# Sheet1.net
KiCad netlist of a schematic drawn in Altium Designer
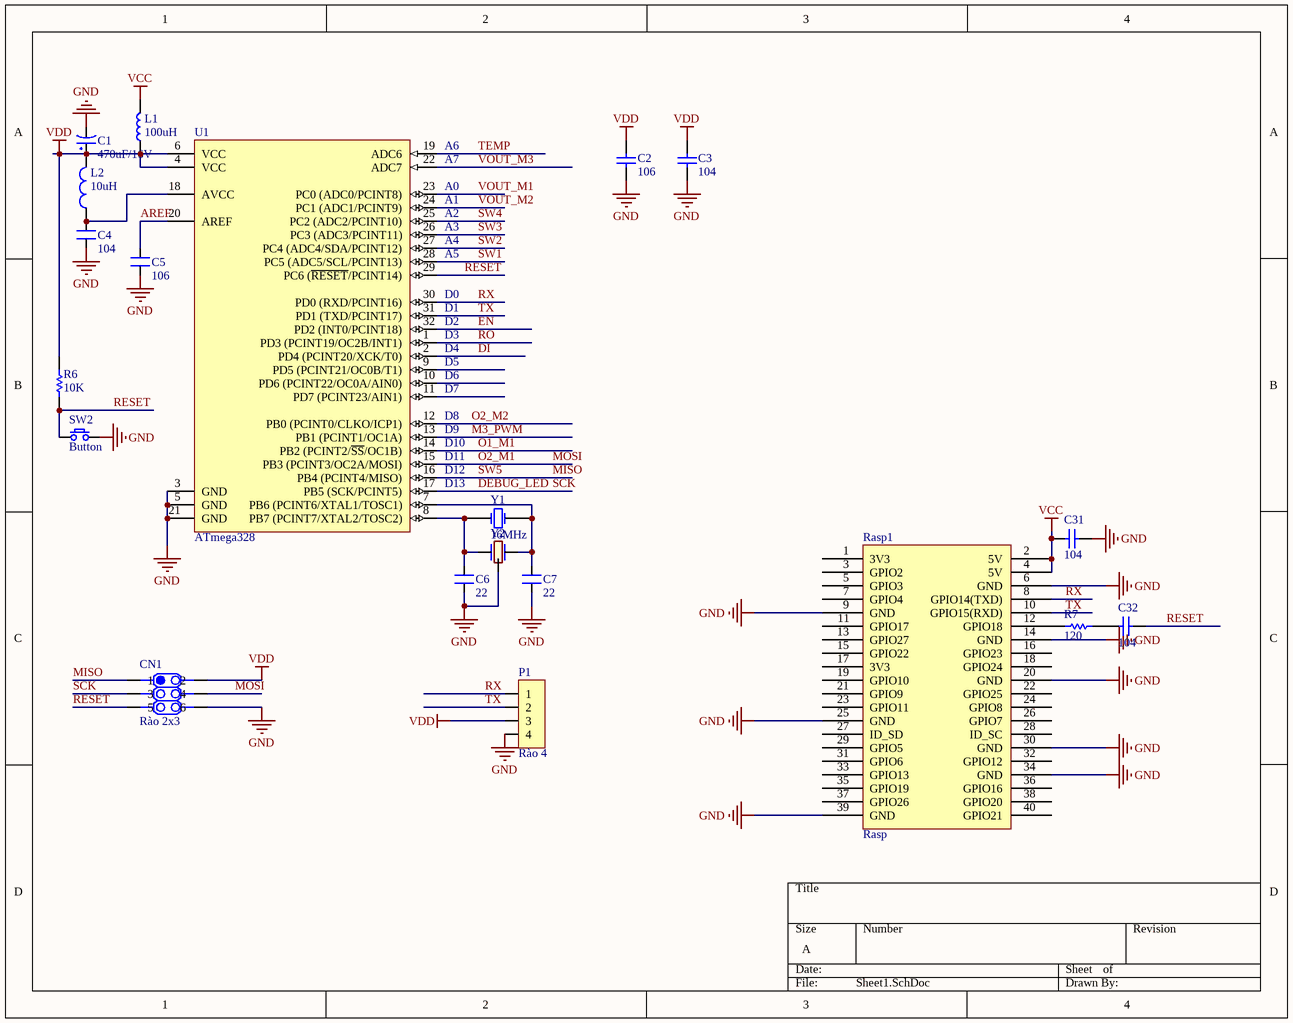
[diagram p0: Sheet1.SchDoc]

(export (version "E")
  (design (tool "Eeschema 10.0.6"))
  (components
    (comp (ref "C1")
      (value "470uF/16V")
      (footprint "WCAP-PSHP 8x8.7x3.1")
      (description "Cap 1000uF/16V - 220uF/50V")
      (libsource (lib "syhaunguyen") (part "CP4"))
    )
    (comp (ref "C2")
      (value "106")
      (footprint "C 0805 (2012)")
      (description "Capacitor non-pol")
      (libsource (lib "BKIT4U_LIB") (part "Capacitor NP"))
    )
    (comp (ref "C3")
      (value "104")
      (footprint "C 0805 (2012)")
      (description "Capacitor non-pol")
      (libsource (lib "BKIT4U_LIB") (part "Capacitor NP"))
    )
    (comp (ref "C4")
      (value "104")
      (footprint "R 0805 (2012)")
      (description "Cap np 104 => 105pF")
      (libsource (lib "syhaunguyen") (part "CN2"))
    )
    (comp (ref "C5")
      (value "106")
      (footprint "R 0805 (2012)")
      (description "Cap np  1pF - 472pF")
      (libsource (lib "syhaunguyen") (part "CN1"))
    )
    (comp (ref "C6")
      (value "22")
      (footprint "C 0805 (2012)")
      (description "Cap np 104 => 105pF")
      (libsource (lib "syhaunguyen") (part "CN2"))
    )
    (comp (ref "C7")
      (value "22")
      (footprint "C 0805 (2012)")
      (description "Cap np 104 => 105pF")
      (libsource (lib "syhaunguyen") (part "CN2"))
    )
    (comp (ref "C31")
      (value "104")
      (footprint "C 0805 (2012)")
      (description "Capacitor non-pol")
      (libsource (lib "BKIT4U_LIB") (part "Capacitor NP"))
    )
    (comp (ref "C32")
      (value "104")
      (footprint "C 0805 (2012)")
      (description "Capacitor non-pol")
      (libsource (lib "BKIT4U_LIB") (part "Capacitor NP"))
    )
    (comp (ref "CN1")
      (value "Rào 2x3")
      (footprint "Header 3x2")
      (description "Header 2x3")
      (fields (field (name "PUBLISHER") "Hoang Nguyen"))
      (libsource (lib "phong") (part "CON.HDR2x3"))
    )
    (comp (ref "L1")
      (value "100uH")
      (footprint "Inductor SMD 0805 (2012)")
      (description "Inductor")
      (libsource (lib "BKIT4U_LIB") (part "Inductor"))
    )
    (comp (ref "L2")
      (value "10uH")
      (footprint "R 0805 (2012)")
      (description "Inductor")
      (libsource (lib "syhaunguyen") (part "L1"))
    )
    (comp (ref "P1")
      (value "Rào 4")
      (footprint "Header 4")
      (description "Header, 4-Pin")
      (libsource (lib "BKIT4U_LIB") (part "Header 4"))
    )
    (comp (ref "R6")
      (value "10K")
      (footprint "R 0805 (2012)")
      (description "Resistor")
      (fields (field (name "PUBLISHER") "Altium Limited"))
      (libsource (lib "phong") (part "Resistor"))
    )
    (comp (ref "R7")
      (value "120")
      (footprint "R 0805 (2012)")
      (description "Resistor")
      (fields (field (name "PUBLISHER") "Altium Limited"))
      (libsource (lib "BKIT4U_LIB") (part "Resistor"))
    )
    (comp (ref "Rasp1")
      (value "Rasp")
      (footprint "Raspberry Pi 3B")
      (libsource (lib "Raspberry Pi 3B") (part "Rasp"))
    )
    (comp (ref "SW2")
      (value "Button")
      (footprint "SW/2/SMD")
      (description "Tact switch 2 pin")
      (libsource (lib "BKIT4U_LIB") (part "SW SPST"))
    )
    (comp (ref "U1")
      (value "ATmega328")
      (footprint "QFP32N")
      (fields (field (name "PUBLISHER") "Altium Limited"))
      (libsource (lib "Atmel Microcontroller 8-Bit megaAVR") (part "ATmega328-AU"))
    )
    (comp (ref "Y1")
      (value "16MHz")
      (footprint "XTAL")
      (description "Crystal Oscillator")
      (fields (field (name "PUBLISHER") "Altium Limited"))
      (libsource (lib "phong") (part "XTAL"))
    )
    (comp (ref "Y2")
      (value "~")
      (footprint "Crystal SMD CSTCE")
      (libsource (lib "BKIT4U_LIB") (part "Crystal CSTCE"))
    )
  )
  (nets
    (net (code "1") (name "/AREF") (class "Default")
      (node (ref "C5") (pin "2") (pinfunction "2_2") (pintype "passive"))
      (node (ref "U1") (pin "20") (pinfunction "AREF_20") (pintype "passive"))
    )
    (net (code "2") (name "/DEBUG_LED") (class "Default")
      (node (ref "CN1") (pin "3") (pinfunction "3_3") (pintype "passive"))
      (node (ref "U1") (pin "17") (pinfunction "PB5_(SCK/PCINT5)_17") (pintype "bidirectional"))
    )
    (net (code "3") (name "/DI") (class "Default")
      (node (ref "U1") (pin "2") (pinfunction "PD4_(PCINT20/XCK/T0)_2") (pintype "bidirectional"))
    )
    (net (code "4") (name "/EN") (class "Default")
      (node (ref "U1") (pin "32") (pinfunction "PD2_(INT0/PCINT18)_32") (pintype "bidirectional"))
    )
    (net (code "5") (name "/M3_PWM") (class "Default")
      (node (ref "U1") (pin "13") (pinfunction "PB1_(PCINT1/OC1A)_13") (pintype "bidirectional"))
    )
    (net (code "6") (name "/MISO") (class "Default")
      (node (ref "CN1") (pin "1") (pinfunction "1_1") (pintype "passive"))
      (node (ref "U1") (pin "16") (pinfunction "PB4_(PCINT4/MISO)_16") (pintype "bidirectional"))
    )
    (net (code "7") (name "/MOSI") (class "Default")
      (node (ref "CN1") (pin "4") (pinfunction "4_4") (pintype "passive"))
      (node (ref "U1") (pin "15") (pinfunction "PB3_(PCINT3/OC2A/MOSI)_15") (pintype "bidirectional"))
    )
    (net (code "8") (name "/O1_M1") (class "Default")
      (node (ref "U1") (pin "14") (pinfunction "PB2_(PCINT2/~{SS}/OC1B)_14") (pintype "bidirectional"))
    )
    (net (code "9") (name "/O2_M2") (class "Default")
      (node (ref "U1") (pin "12") (pinfunction "PB0_(PCINT0/CLKO/ICP1)_12") (pintype "bidirectional"))
    )
    (net (code "10") (name "/RESET") (class "Default")
      (node (ref "C32") (pin "2") (pinfunction "2_2") (pintype "passive"))
      (node (ref "CN1") (pin "5") (pinfunction "5_5") (pintype "passive"))
      (node (ref "R6") (pin "1") (pinfunction "1_1") (pintype "passive"))
      (node (ref "SW2") (pin "1") (pinfunction "1_1") (pintype "passive"))
      (node (ref "U1") (pin "29") (pinfunction "PC6_(~{RESET}/PCINT14)_29") (pintype "bidirectional"))
    )
    (net (code "11") (name "/RO") (class "Default")
      (node (ref "U1") (pin "1") (pinfunction "PD3_(PCINT19/OC2B/INT1)_1") (pintype "bidirectional"))
    )
    (net (code "12") (name "/RX") (class "Default")
      (node (ref "P1") (pin "1") (pinfunction "1_1") (pintype "passive"))
      (node (ref "Rasp1") (pin "8") (pinfunction "GPIO14(TXD)_8") (pintype "passive"))
      (node (ref "U1") (pin "30") (pinfunction "PD0_(RXD/PCINT16)_30") (pintype "bidirectional"))
    )
    (net (code "13") (name "/SW1") (class "Default")
      (node (ref "U1") (pin "28") (pinfunction "PC5_(ADC5/SCL/PCINT13)_28") (pintype "bidirectional"))
    )
    (net (code "14") (name "/SW2") (class "Default")
      (node (ref "U1") (pin "27") (pinfunction "PC4_(ADC4/SDA/PCINT12)_27") (pintype "bidirectional"))
    )
    (net (code "15") (name "/SW3") (class "Default")
      (node (ref "U1") (pin "26") (pinfunction "PC3_(ADC3/PCINT11)_26") (pintype "bidirectional"))
    )
    (net (code "16") (name "/SW4") (class "Default")
      (node (ref "U1") (pin "25") (pinfunction "PC2_(ADC2/PCINT10)_25") (pintype "bidirectional"))
    )
    (net (code "17") (name "/TEMP") (class "Default")
      (node (ref "U1") (pin "19") (pinfunction "ADC6_19") (pintype "input"))
    )
    (net (code "18") (name "/TX") (class "Default")
      (node (ref "P1") (pin "2") (pinfunction "2_2") (pintype "passive"))
      (node (ref "Rasp1") (pin "10") (pinfunction "GPIO15(RXD)_10") (pintype "passive"))
      (node (ref "U1") (pin "31") (pinfunction "PD1_(TXD/PCINT17)_31") (pintype "bidirectional"))
    )
    (net (code "19") (name "/VOUT_M1") (class "Default")
      (node (ref "U1") (pin "23") (pinfunction "PC0_(ADC0/PCINT8)_23") (pintype "bidirectional"))
    )
    (net (code "20") (name "/VOUT_M2") (class "Default")
      (node (ref "U1") (pin "24") (pinfunction "PC1_(ADC1/PCINT9)_24") (pintype "bidirectional"))
    )
    (net (code "21") (name "/VOUT_M3") (class "Default")
      (node (ref "U1") (pin "22") (pinfunction "ADC7_22") (pintype "input"))
    )
    (net (code "22") (name "GND") (class "Default")
      (node (ref "C1") (pin "2") (pinfunction "2_2") (pintype "passive"))
      (node (ref "C2") (pin "2") (pinfunction "2_2") (pintype "passive"))
      (node (ref "C3") (pin "2") (pinfunction "2_2") (pintype "passive"))
      (node (ref "C31") (pin "2") (pinfunction "2_2") (pintype "passive"))
      (node (ref "C4") (pin "1") (pinfunction "1_1") (pintype "passive"))
      (node (ref "C5") (pin "1") (pinfunction "1_1") (pintype "passive"))
      (node (ref "C6") (pin "1") (pinfunction "1_1") (pintype "passive"))
      (node (ref "C7") (pin "1") (pinfunction "1_1") (pintype "passive"))
      (node (ref "CN1") (pin "6") (pinfunction "6_6") (pintype "passive"))
      (node (ref "P1") (pin "4") (pinfunction "4_4") (pintype "passive"))
      (node (ref "Rasp1") (pin "14") (pinfunction "GND_14") (pintype "passive"))
      (node (ref "Rasp1") (pin "20") (pinfunction "GND_20") (pintype "passive"))
      (node (ref "Rasp1") (pin "25") (pinfunction "GND_25") (pintype "passive"))
      (node (ref "Rasp1") (pin "30") (pinfunction "GND_30") (pintype "passive"))
      (node (ref "Rasp1") (pin "34") (pinfunction "GND_34") (pintype "passive"))
      (node (ref "Rasp1") (pin "39") (pinfunction "GND_39") (pintype "passive"))
      (node (ref "Rasp1") (pin "6") (pinfunction "GND_6") (pintype "passive"))
      (node (ref "Rasp1") (pin "9") (pinfunction "GND_9") (pintype "passive"))
      (node (ref "SW2") (pin "2") (pinfunction "2_2") (pintype "passive"))
      (node (ref "U1") (pin "21") (pinfunction "GND_21") (pintype "power_in"))
      (node (ref "U1") (pin "3") (pinfunction "GND_3") (pintype "power_in"))
      (node (ref "U1") (pin "5") (pinfunction "GND_5") (pintype "power_in"))
      (node (ref "Y2") (pin "2") (pinfunction "2_2") (pintype "passive"))
    )
    (net (code "23") (name "Net-(C32-Pad1)") (class "Default")
      (node (ref "C32") (pin "1") (pinfunction "1_1") (pintype "passive"))
      (node (ref "R7") (pin "1") (pinfunction "1_1") (pintype "passive"))
    )
    (net (code "24") (name "Net-(Rasp1-GPIO18)") (class "Default")
      (node (ref "R7") (pin "2") (pinfunction "2_2") (pintype "passive"))
      (node (ref "Rasp1") (pin "12") (pinfunction "GPIO18_12") (pintype "passive"))
    )
    (net (code "25") (name "Net-(U1-AVCC)") (class "Default")
      (node (ref "C4") (pin "2") (pinfunction "2_2") (pintype "passive"))
      (node (ref "L2") (pin "1") (pinfunction "1_1") (pintype "passive"))
      (node (ref "U1") (pin "18") (pinfunction "AVCC_18") (pintype "power_in"))
    )
    (net (code "26") (name "Net-(U1-PB6_(PCINT6{slash}XTAL1{slash}TOSC1))") (class "Default")
      (node (ref "C7") (pin "2") (pinfunction "2_2") (pintype "passive"))
      (node (ref "U1") (pin "7") (pinfunction "PB6_(PCINT6/XTAL1/TOSC1)_7") (pintype "bidirectional"))
      (node (ref "Y1") (pin "2") (pinfunction "OSC2_2") (pintype "passive"))
      (node (ref "Y2") (pin "1") (pinfunction "1_1") (pintype "passive"))
    )
    (net (code "27") (name "Net-(U1-PB7_(PCINT7{slash}XTAL2{slash}TOSC2))") (class "Default")
      (node (ref "C6") (pin "2") (pinfunction "2_2") (pintype "passive"))
      (node (ref "U1") (pin "8") (pinfunction "PB7_(PCINT7/XTAL2/TOSC2)_8") (pintype "bidirectional"))
      (node (ref "Y1") (pin "1") (pinfunction "OSC1_1") (pintype "passive"))
      (node (ref "Y2") (pin "3") (pinfunction "3_3") (pintype "passive"))
    )
    (net (code "28") (name "VCC") (class "Default")
      (node (ref "C31") (pin "1") (pinfunction "1_1") (pintype "passive"))
      (node (ref "L1") (pin "2") (pinfunction "2_2") (pintype "passive"))
      (node (ref "Rasp1") (pin "2") (pinfunction "5V_2") (pintype "passive"))
      (node (ref "Rasp1") (pin "4") (pinfunction "5V_4") (pintype "passive"))
    )
    (net (code "29") (name "VDD") (class "Default")
      (node (ref "C1") (pin "1") (pinfunction "1_1") (pintype "passive"))
      (node (ref "C2") (pin "1") (pinfunction "1_1") (pintype "passive"))
      (node (ref "C3") (pin "1") (pinfunction "1_1") (pintype "passive"))
      (node (ref "CN1") (pin "2") (pinfunction "2_2") (pintype "passive"))
      (node (ref "L1") (pin "1") (pinfunction "1_1") (pintype "passive"))
      (node (ref "L2") (pin "2") (pinfunction "2_2") (pintype "passive"))
      (node (ref "P1") (pin "3") (pinfunction "3_3") (pintype "passive"))
      (node (ref "R6") (pin "2") (pinfunction "2_2") (pintype "passive"))
      (node (ref "U1") (pin "4") (pinfunction "VCC_4") (pintype "power_in"))
      (node (ref "U1") (pin "6") (pinfunction "VCC_6") (pintype "power_in"))
    )
    (net (code "30") (name "unconnected-(Rasp1-3V3-Pad1)") (class "Default")
      (node (ref "Rasp1") (pin "1") (pinfunction "3V3_1") (pintype "passive"))
    )
    (net (code "31") (name "unconnected-(Rasp1-3V3-Pad17)") (class "Default")
      (node (ref "Rasp1") (pin "17") (pinfunction "3V3_17") (pintype "passive"))
    )
    (net (code "32") (name "unconnected-(Rasp1-GPIO2-Pad3)") (class "Default")
      (node (ref "Rasp1") (pin "3") (pinfunction "GPIO2_3") (pintype "passive"))
    )
    (net (code "33") (name "unconnected-(Rasp1-GPIO3-Pad5)") (class "Default")
      (node (ref "Rasp1") (pin "5") (pinfunction "GPIO3_5") (pintype "passive"))
    )
    (net (code "34") (name "unconnected-(Rasp1-GPIO4-Pad7)") (class "Default")
      (node (ref "Rasp1") (pin "7") (pinfunction "GPIO4_7") (pintype "passive"))
    )
    (net (code "35") (name "unconnected-(Rasp1-GPIO5-Pad29)") (class "Default")
      (node (ref "Rasp1") (pin "29") (pinfunction "GPIO5_29") (pintype "passive"))
    )
    (net (code "36") (name "unconnected-(Rasp1-GPIO6-Pad31)") (class "Default")
      (node (ref "Rasp1") (pin "31") (pinfunction "GPIO6_31") (pintype "passive"))
    )
    (net (code "37") (name "unconnected-(Rasp1-GPIO7-Pad26)") (class "Default")
      (node (ref "Rasp1") (pin "26") (pinfunction "GPIO7_26") (pintype "passive"))
    )
    (net (code "38") (name "unconnected-(Rasp1-GPIO8-Pad24)") (class "Default")
      (node (ref "Rasp1") (pin "24") (pinfunction "GPIO8_24") (pintype "passive"))
    )
    (net (code "39") (name "unconnected-(Rasp1-GPIO9-Pad21)") (class "Default")
      (node (ref "Rasp1") (pin "21") (pinfunction "GPIO9_21") (pintype "passive"))
    )
    (net (code "40") (name "unconnected-(Rasp1-GPIO10-Pad19)") (class "Default")
      (node (ref "Rasp1") (pin "19") (pinfunction "GPIO10_19") (pintype "passive"))
    )
    (net (code "41") (name "unconnected-(Rasp1-GPIO11-Pad23)") (class "Default")
      (node (ref "Rasp1") (pin "23") (pinfunction "GPIO11_23") (pintype "passive"))
    )
    (net (code "42") (name "unconnected-(Rasp1-GPIO12-Pad32)") (class "Default")
      (node (ref "Rasp1") (pin "32") (pinfunction "GPIO12_32") (pintype "passive"))
    )
    (net (code "43") (name "unconnected-(Rasp1-GPIO13-Pad33)") (class "Default")
      (node (ref "Rasp1") (pin "33") (pinfunction "GPIO13_33") (pintype "passive"))
    )
    (net (code "44") (name "unconnected-(Rasp1-GPIO16-Pad36)") (class "Default")
      (node (ref "Rasp1") (pin "36") (pinfunction "GPIO16_36") (pintype "passive"))
    )
    (net (code "45") (name "unconnected-(Rasp1-GPIO17-Pad11)") (class "Default")
      (node (ref "Rasp1") (pin "11") (pinfunction "GPIO17_11") (pintype "passive"))
    )
    (net (code "46") (name "unconnected-(Rasp1-GPIO19-Pad35)") (class "Default")
      (node (ref "Rasp1") (pin "35") (pinfunction "GPIO19_35") (pintype "passive"))
    )
    (net (code "47") (name "unconnected-(Rasp1-GPIO20-Pad38)") (class "Default")
      (node (ref "Rasp1") (pin "38") (pinfunction "GPIO20_38") (pintype "passive"))
    )
    (net (code "48") (name "unconnected-(Rasp1-GPIO21-Pad40)") (class "Default")
      (node (ref "Rasp1") (pin "40") (pinfunction "GPIO21_40") (pintype "passive"))
    )
    (net (code "49") (name "unconnected-(Rasp1-GPIO22-Pad15)") (class "Default")
      (node (ref "Rasp1") (pin "15") (pinfunction "GPIO22_15") (pintype "passive"))
    )
    (net (code "50") (name "unconnected-(Rasp1-GPIO23-Pad16)") (class "Default")
      (node (ref "Rasp1") (pin "16") (pinfunction "GPIO23_16") (pintype "passive"))
    )
    (net (code "51") (name "unconnected-(Rasp1-GPIO24-Pad18)") (class "Default")
      (node (ref "Rasp1") (pin "18") (pinfunction "GPIO24_18") (pintype "passive"))
    )
    (net (code "52") (name "unconnected-(Rasp1-GPIO25-Pad22)") (class "Default")
      (node (ref "Rasp1") (pin "22") (pinfunction "GPIO25_22") (pintype "passive"))
    )
    (net (code "53") (name "unconnected-(Rasp1-GPIO26-Pad37)") (class "Default")
      (node (ref "Rasp1") (pin "37") (pinfunction "GPIO26_37") (pintype "passive"))
    )
    (net (code "54") (name "unconnected-(Rasp1-GPIO27-Pad13)") (class "Default")
      (node (ref "Rasp1") (pin "13") (pinfunction "GPIO27_13") (pintype "passive"))
    )
    (net (code "55") (name "unconnected-(Rasp1-ID_SC-Pad28)") (class "Default")
      (node (ref "Rasp1") (pin "28") (pinfunction "ID_SC_28") (pintype "passive"))
    )
    (net (code "56") (name "unconnected-(Rasp1-ID_SD-Pad27)") (class "Default")
      (node (ref "Rasp1") (pin "27") (pinfunction "ID_SD_27") (pintype "passive"))
    )
    (net (code "57") (name "unconnected-(U1-PD5_(PCINT21{slash}OC0B{slash}T1)-Pad9)") (class "Default")
      (node (ref "U1") (pin "9") (pinfunction "PD5_(PCINT21/OC0B/T1)_9") (pintype "bidirectional"))
    )
    (net (code "58") (name "unconnected-(U1-PD6_(PCINT22{slash}OC0A{slash}AIN0)-Pad10)") (class "Default")
      (node (ref "U1") (pin "10") (pinfunction "PD6_(PCINT22/OC0A/AIN0)_10") (pintype "bidirectional"))
    )
    (net (code "59") (name "unconnected-(U1-PD7_(PCINT23{slash}AIN1)-Pad11)") (class "Default")
      (node (ref "U1") (pin "11") (pinfunction "PD7_(PCINT23/AIN1)_11") (pintype "bidirectional"))
    )
  )
)
